# bob-spark-shield.net
KiCad netlist of a schematic drawn in EAGLE
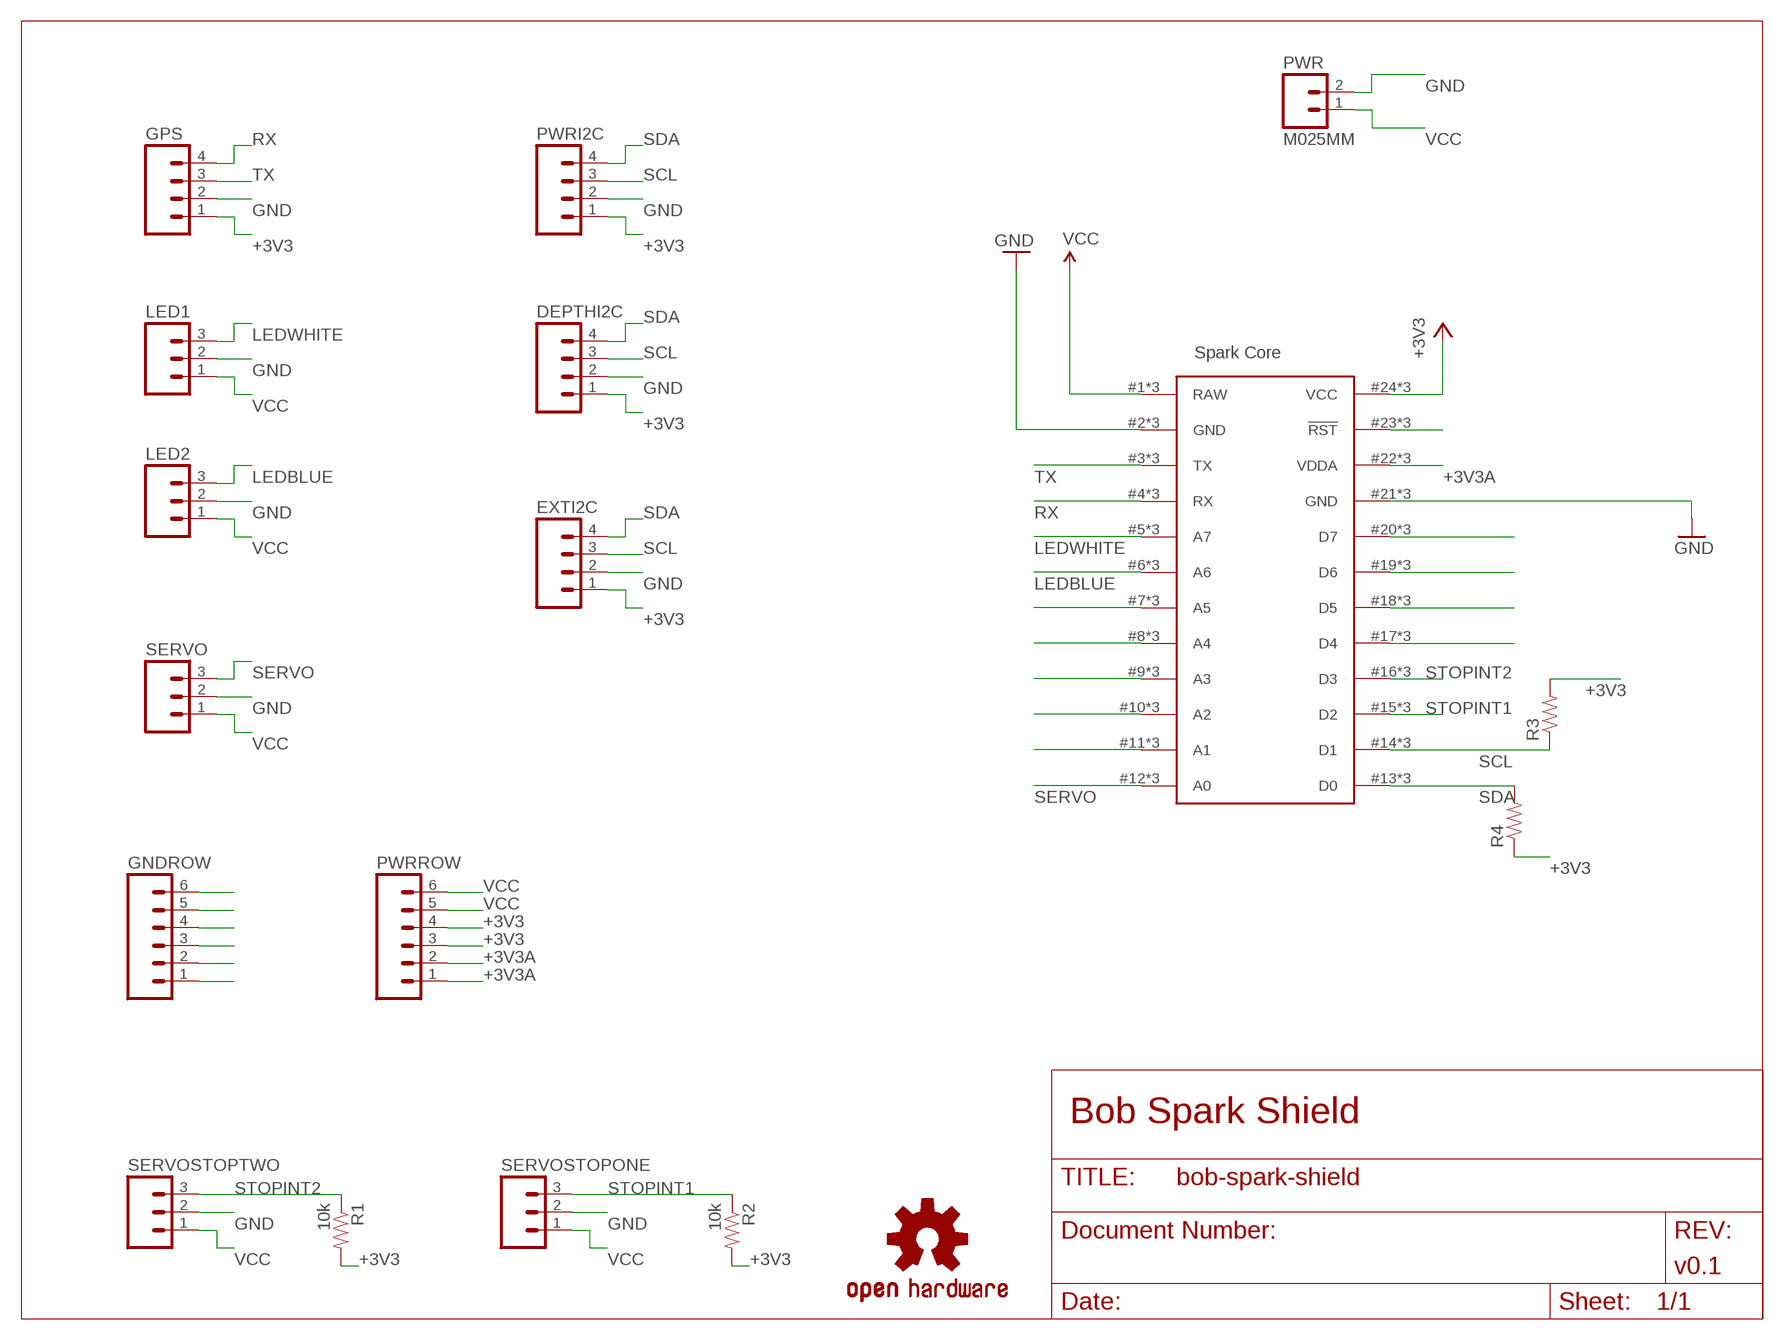
[diagram p0: schematic, sheet 1]

(export (version "E")
  (design (tool "Eeschema 10.0.6"))
  (components
    (comp (ref "DEPTHI2C")
      (value "M04LOCK")
      (footprint "eagle-import:1X04_LOCK")
      (libsource (lib "eagle-import") (part "M04LOCK"))
    )
    (comp (ref "EXTI2C")
      (value "M04LOCK")
      (footprint "eagle-import:1X04_LOCK")
      (libsource (lib "eagle-import") (part "M04LOCK"))
    )
    (comp (ref "GNDROW")
      (value "M06LOCK")
      (footprint "eagle-import:1X06_LOCK")
      (libsource (lib "eagle-import") (part "M06LOCK"))
    )
    (comp (ref "GPS")
      (value "M04LOCK")
      (footprint "eagle-import:1X04_LOCK")
      (libsource (lib "eagle-import") (part "M04LOCK"))
    )
    (comp (ref "LED1")
      (value "M03LOCK")
      (footprint "eagle-import:1X03_LOCK")
      (libsource (lib "eagle-import") (part "M03LOCK"))
    )
    (comp (ref "LED2")
      (value "M03LOCK")
      (footprint "eagle-import:1X03_LOCK")
      (libsource (lib "eagle-import") (part "M03LOCK"))
    )
    (comp (ref "LOGO1")
      (value "OSHW-LOGOM")
      (footprint "eagle-import:OSHW-LOGO-M")
      (libsource (lib "eagle-import") (part "OSHW-LOGOM"))
    )
    (comp (ref "PWR")
      (value "M025MM")
      (footprint "eagle-import:SCREWTERMINAL-5MM-2")
      (libsource (lib "eagle-import") (part "M025MM"))
    )
    (comp (ref "PWRI2C")
      (value "M04LOCK")
      (footprint "eagle-import:1X04_LOCK")
      (libsource (lib "eagle-import") (part "M04LOCK"))
    )
    (comp (ref "PWRROW")
      (value "M06LOCK")
      (footprint "eagle-import:1X06_LOCK")
      (libsource (lib "eagle-import") (part "M06LOCK"))
    )
    (comp (ref "R1")
      (value "10k")
      (footprint "eagle-import:0805")
      (libsource (lib "eagle-import") (part "RESISTOR0805-RES"))
    )
    (comp (ref "R2")
      (value "10k")
      (footprint "eagle-import:0805")
      (libsource (lib "eagle-import") (part "RESISTOR0805-RES"))
    )
    (comp (ref "R3")
      (value "RESISTOR0805-RES")
      (footprint "eagle-import:0805")
      (libsource (lib "eagle-import") (part "RESISTOR0805-RES"))
    )
    (comp (ref "R4")
      (value "RESISTOR0805-RES")
      (footprint "eagle-import:0805")
      (libsource (lib "eagle-import") (part "RESISTOR0805-RES"))
    )
    (comp (ref "SERVO")
      (value "M03LOCK")
      (footprint "eagle-import:1X03_LOCK")
      (libsource (lib "eagle-import") (part "M03LOCK"))
    )
    (comp (ref "SERVOSTOPONE")
      (value "M03LOCK")
      (footprint "eagle-import:1X03_LOCK")
      (libsource (lib "eagle-import") (part "M03LOCK"))
    )
    (comp (ref "SERVOSTOPTWO")
      (value "M03LOCK")
      (footprint "eagle-import:1X03_LOCK")
      (libsource (lib "eagle-import") (part "M03LOCK"))
    )
    (comp (ref "U$1")
      (value "SPARK_CORE")
      (footprint "eagle-import:SPARK_CORE_STACKABLE")
      (libsource (lib "eagle-import") (part "SPARK_CORE"))
    )
  )
  (nets
    (net (code "1") (name "+3V3") (class "Default")
      (node (ref "DEPTHI2C") (pin "1") (pinfunction "1_1") (pintype "passive"))
      (node (ref "EXTI2C") (pin "1") (pinfunction "1_1") (pintype "passive"))
      (node (ref "GPS") (pin "1") (pinfunction "1_1") (pintype "passive"))
      (node (ref "PWRI2C") (pin "1") (pinfunction "1_1") (pintype "passive"))
      (node (ref "PWRROW") (pin "3") (pinfunction "3_3") (pintype "passive"))
      (node (ref "PWRROW") (pin "4") (pinfunction "4_4") (pintype "passive"))
      (node (ref "R1") (pin "2") (pinfunction "2_2") (pintype "passive"))
      (node (ref "R2") (pin "2") (pinfunction "2_2") (pintype "passive"))
      (node (ref "R3") (pin "2") (pinfunction "2_2") (pintype "passive"))
      (node (ref "R4") (pin "1") (pinfunction "1_1") (pintype "passive"))
      (node (ref "U$1") (pin "#24") (pinfunction "VCC_#24") (pintype "power_in"))
      (node (ref "U$1") (pin "24") (pinfunction "VCC_24") (pintype "power_in"))
      (node (ref "U$1") (pin "@24") (pinfunction "VCC_@24") (pintype "power_in"))
    )
    (net (code "2") (name "/+3V3A") (class "Default")
      (node (ref "PWRROW") (pin "1") (pinfunction "1_1") (pintype "passive"))
      (node (ref "PWRROW") (pin "2") (pinfunction "2_2") (pintype "passive"))
      (node (ref "U$1") (pin "#22") (pinfunction "VDDA_#22") (pintype "power_in"))
      (node (ref "U$1") (pin "22") (pinfunction "VDDA_22") (pintype "power_in"))
      (node (ref "U$1") (pin "@22") (pinfunction "VDDA_@22") (pintype "power_in"))
    )
    (net (code "3") (name "/LEDBLUE") (class "Default")
      (node (ref "LED2") (pin "3") (pinfunction "3_3") (pintype "passive"))
      (node (ref "U$1") (pin "#6") (pinfunction "A6_#6") (pintype "bidirectional"))
      (node (ref "U$1") (pin "6") (pinfunction "A6_6") (pintype "bidirectional"))
      (node (ref "U$1") (pin "@6") (pinfunction "A6_@6") (pintype "bidirectional"))
    )
    (net (code "4") (name "/LEDWHITE") (class "Default")
      (node (ref "LED1") (pin "3") (pinfunction "3_3") (pintype "passive"))
      (node (ref "U$1") (pin "#5") (pinfunction "A7_#5") (pintype "bidirectional"))
      (node (ref "U$1") (pin "5") (pinfunction "A7_5") (pintype "bidirectional"))
      (node (ref "U$1") (pin "@5") (pinfunction "A7_@5") (pintype "bidirectional"))
    )
    (net (code "5") (name "/RX") (class "Default")
      (node (ref "GPS") (pin "4") (pinfunction "4_4") (pintype "passive"))
      (node (ref "U$1") (pin "#4") (pinfunction "RX_#4") (pintype "bidirectional"))
      (node (ref "U$1") (pin "4") (pinfunction "RX_4") (pintype "bidirectional"))
      (node (ref "U$1") (pin "@4") (pinfunction "RX_@4") (pintype "bidirectional"))
    )
    (net (code "6") (name "/SCL") (class "Default")
      (node (ref "DEPTHI2C") (pin "3") (pinfunction "3_3") (pintype "passive"))
      (node (ref "EXTI2C") (pin "3") (pinfunction "3_3") (pintype "passive"))
      (node (ref "PWRI2C") (pin "3") (pinfunction "3_3") (pintype "passive"))
      (node (ref "R3") (pin "1") (pinfunction "1_1") (pintype "passive"))
      (node (ref "U$1") (pin "#14") (pinfunction "D1_#14") (pintype "bidirectional"))
      (node (ref "U$1") (pin "14") (pinfunction "D1_14") (pintype "bidirectional"))
      (node (ref "U$1") (pin "@14") (pinfunction "D1_@14") (pintype "bidirectional"))
    )
    (net (code "7") (name "/SDA") (class "Default")
      (node (ref "DEPTHI2C") (pin "4") (pinfunction "4_4") (pintype "passive"))
      (node (ref "EXTI2C") (pin "4") (pinfunction "4_4") (pintype "passive"))
      (node (ref "PWRI2C") (pin "4") (pinfunction "4_4") (pintype "passive"))
      (node (ref "R4") (pin "2") (pinfunction "2_2") (pintype "passive"))
      (node (ref "U$1") (pin "#13") (pinfunction "D0_#13") (pintype "bidirectional"))
      (node (ref "U$1") (pin "13") (pinfunction "D0_13") (pintype "bidirectional"))
      (node (ref "U$1") (pin "@13") (pinfunction "D0_@13") (pintype "bidirectional"))
    )
    (net (code "8") (name "/SERVO") (class "Default")
      (node (ref "SERVO") (pin "3") (pinfunction "3_3") (pintype "passive"))
      (node (ref "U$1") (pin "#12") (pinfunction "A0_#12") (pintype "bidirectional"))
      (node (ref "U$1") (pin "12") (pinfunction "A0_12") (pintype "bidirectional"))
      (node (ref "U$1") (pin "@12") (pinfunction "A0_@12") (pintype "bidirectional"))
    )
    (net (code "9") (name "/STOPINT1") (class "Default")
      (node (ref "R2") (pin "1") (pinfunction "1_1") (pintype "passive"))
      (node (ref "SERVOSTOPONE") (pin "3") (pinfunction "3_3") (pintype "passive"))
      (node (ref "U$1") (pin "#15") (pinfunction "D2_#15") (pintype "bidirectional"))
      (node (ref "U$1") (pin "15") (pinfunction "D2_15") (pintype "bidirectional"))
      (node (ref "U$1") (pin "@15") (pinfunction "D2_@15") (pintype "bidirectional"))
    )
    (net (code "10") (name "/STOPINT2") (class "Default")
      (node (ref "R1") (pin "1") (pinfunction "1_1") (pintype "passive"))
      (node (ref "SERVOSTOPTWO") (pin "3") (pinfunction "3_3") (pintype "passive"))
      (node (ref "U$1") (pin "#16") (pinfunction "D3_#16") (pintype "bidirectional"))
      (node (ref "U$1") (pin "16") (pinfunction "D3_16") (pintype "bidirectional"))
      (node (ref "U$1") (pin "@16") (pinfunction "D3_@16") (pintype "bidirectional"))
    )
    (net (code "11") (name "/TX") (class "Default")
      (node (ref "GPS") (pin "3") (pinfunction "3_3") (pintype "passive"))
      (node (ref "U$1") (pin "#3") (pinfunction "TX_#3") (pintype "bidirectional"))
      (node (ref "U$1") (pin "3") (pinfunction "TX_3") (pintype "bidirectional"))
      (node (ref "U$1") (pin "@3") (pinfunction "TX_@3") (pintype "bidirectional"))
    )
    (net (code "12") (name "GND") (class "Default")
      (node (ref "DEPTHI2C") (pin "2") (pinfunction "2_2") (pintype "passive"))
      (node (ref "EXTI2C") (pin "2") (pinfunction "2_2") (pintype "passive"))
      (node (ref "GNDROW") (pin "1") (pinfunction "1_1") (pintype "passive"))
      (node (ref "GNDROW") (pin "2") (pinfunction "2_2") (pintype "passive"))
      (node (ref "GNDROW") (pin "3") (pinfunction "3_3") (pintype "passive"))
      (node (ref "GNDROW") (pin "4") (pinfunction "4_4") (pintype "passive"))
      (node (ref "GNDROW") (pin "5") (pinfunction "5_5") (pintype "passive"))
      (node (ref "GNDROW") (pin "6") (pinfunction "6_6") (pintype "passive"))
      (node (ref "GPS") (pin "2") (pinfunction "2_2") (pintype "passive"))
      (node (ref "LED1") (pin "2") (pinfunction "2_2") (pintype "passive"))
      (node (ref "LED2") (pin "2") (pinfunction "2_2") (pintype "passive"))
      (node (ref "PWR") (pin "2") (pinfunction "2_2") (pintype "passive"))
      (node (ref "PWRI2C") (pin "2") (pinfunction "2_2") (pintype "passive"))
      (node (ref "SERVO") (pin "2") (pinfunction "2_2") (pintype "passive"))
      (node (ref "SERVOSTOPONE") (pin "2") (pinfunction "2_2") (pintype "passive"))
      (node (ref "SERVOSTOPTWO") (pin "2") (pinfunction "2_2") (pintype "passive"))
      (node (ref "U$1") (pin "#2") (pinfunction "GND_#2") (pintype "power_in"))
      (node (ref "U$1") (pin "#21") (pinfunction "GND_#21") (pintype "power_in"))
      (node (ref "U$1") (pin "2") (pinfunction "GND_2") (pintype "power_in"))
      (node (ref "U$1") (pin "21") (pinfunction "GND_21") (pintype "power_in"))
      (node (ref "U$1") (pin "@2") (pinfunction "GND_@2") (pintype "power_in"))
      (node (ref "U$1") (pin "@21") (pinfunction "GND_@21") (pintype "power_in"))
    )
    (net (code "13") (name "Net-(U$1-A1-Pad#11)") (class "Default")
      (node (ref "U$1") (pin "#11") (pinfunction "A1_#11") (pintype "bidirectional"))
      (node (ref "U$1") (pin "11") (pinfunction "A1_11") (pintype "bidirectional"))
      (node (ref "U$1") (pin "@11") (pinfunction "A1_@11") (pintype "bidirectional"))
    )
    (net (code "14") (name "Net-(U$1-A2-Pad#10)") (class "Default")
      (node (ref "U$1") (pin "#10") (pinfunction "A2_#10") (pintype "bidirectional"))
      (node (ref "U$1") (pin "10") (pinfunction "A2_10") (pintype "bidirectional"))
      (node (ref "U$1") (pin "@10") (pinfunction "A2_@10") (pintype "bidirectional"))
    )
    (net (code "15") (name "Net-(U$1-A3-Pad#9)") (class "Default")
      (node (ref "U$1") (pin "#9") (pinfunction "A3_#9") (pintype "bidirectional"))
      (node (ref "U$1") (pin "9") (pinfunction "A3_9") (pintype "bidirectional"))
      (node (ref "U$1") (pin "@9") (pinfunction "A3_@9") (pintype "bidirectional"))
    )
    (net (code "16") (name "Net-(U$1-A4-Pad#8)") (class "Default")
      (node (ref "U$1") (pin "#8") (pinfunction "A4_#8") (pintype "bidirectional"))
      (node (ref "U$1") (pin "8") (pinfunction "A4_8") (pintype "bidirectional"))
      (node (ref "U$1") (pin "@8") (pinfunction "A4_@8") (pintype "bidirectional"))
    )
    (net (code "17") (name "Net-(U$1-A5-Pad#7)") (class "Default")
      (node (ref "U$1") (pin "#7") (pinfunction "A5_#7") (pintype "bidirectional"))
      (node (ref "U$1") (pin "7") (pinfunction "A5_7") (pintype "bidirectional"))
      (node (ref "U$1") (pin "@7") (pinfunction "A5_@7") (pintype "bidirectional"))
    )
    (net (code "18") (name "Net-(U$1-D4-Pad#17)") (class "Default")
      (node (ref "U$1") (pin "#17") (pinfunction "D4_#17") (pintype "bidirectional"))
      (node (ref "U$1") (pin "17") (pinfunction "D4_17") (pintype "bidirectional"))
      (node (ref "U$1") (pin "@17") (pinfunction "D4_@17") (pintype "bidirectional"))
    )
    (net (code "19") (name "Net-(U$1-D5-Pad#18)") (class "Default")
      (node (ref "U$1") (pin "#18") (pinfunction "D5_#18") (pintype "bidirectional"))
      (node (ref "U$1") (pin "18") (pinfunction "D5_18") (pintype "bidirectional"))
      (node (ref "U$1") (pin "@18") (pinfunction "D5_@18") (pintype "bidirectional"))
    )
    (net (code "20") (name "Net-(U$1-D6-Pad#19)") (class "Default")
      (node (ref "U$1") (pin "#19") (pinfunction "D6_#19") (pintype "bidirectional"))
      (node (ref "U$1") (pin "19") (pinfunction "D6_19") (pintype "bidirectional"))
      (node (ref "U$1") (pin "@19") (pinfunction "D6_@19") (pintype "bidirectional"))
    )
    (net (code "21") (name "Net-(U$1-D7-Pad#20)") (class "Default")
      (node (ref "U$1") (pin "#20") (pinfunction "D7_#20") (pintype "bidirectional"))
      (node (ref "U$1") (pin "20") (pinfunction "D7_20") (pintype "bidirectional"))
      (node (ref "U$1") (pin "@20") (pinfunction "D7_@20") (pintype "bidirectional"))
    )
    (net (code "22") (name "Net-(U$1-~{RST}-Pad#23)") (class "Default")
      (node (ref "U$1") (pin "#23") (pinfunction "~{RST}_#23") (pintype "bidirectional"))
      (node (ref "U$1") (pin "23") (pinfunction "~{RST}_23") (pintype "bidirectional"))
      (node (ref "U$1") (pin "@23") (pinfunction "~{RST}_@23") (pintype "bidirectional"))
    )
    (net (code "23") (name "VCC") (class "Default")
      (node (ref "LED1") (pin "1") (pinfunction "1_1") (pintype "passive"))
      (node (ref "LED2") (pin "1") (pinfunction "1_1") (pintype "passive"))
      (node (ref "PWR") (pin "1") (pinfunction "1_1") (pintype "passive"))
      (node (ref "PWRROW") (pin "5") (pinfunction "5_5") (pintype "passive"))
      (node (ref "PWRROW") (pin "6") (pinfunction "6_6") (pintype "passive"))
      (node (ref "SERVO") (pin "1") (pinfunction "1_1") (pintype "passive"))
      (node (ref "SERVOSTOPONE") (pin "1") (pinfunction "1_1") (pintype "passive"))
      (node (ref "SERVOSTOPTWO") (pin "1") (pinfunction "1_1") (pintype "passive"))
      (node (ref "U$1") (pin "#1") (pinfunction "RAW_#1") (pintype "power_in"))
      (node (ref "U$1") (pin "1") (pinfunction "RAW_1") (pintype "power_in"))
      (node (ref "U$1") (pin "@1") (pinfunction "RAW_@1") (pintype "power_in"))
    )
  )
)
